# TPS63031_breakout.net
KiCad netlist of a schematic drawn in EAGLE
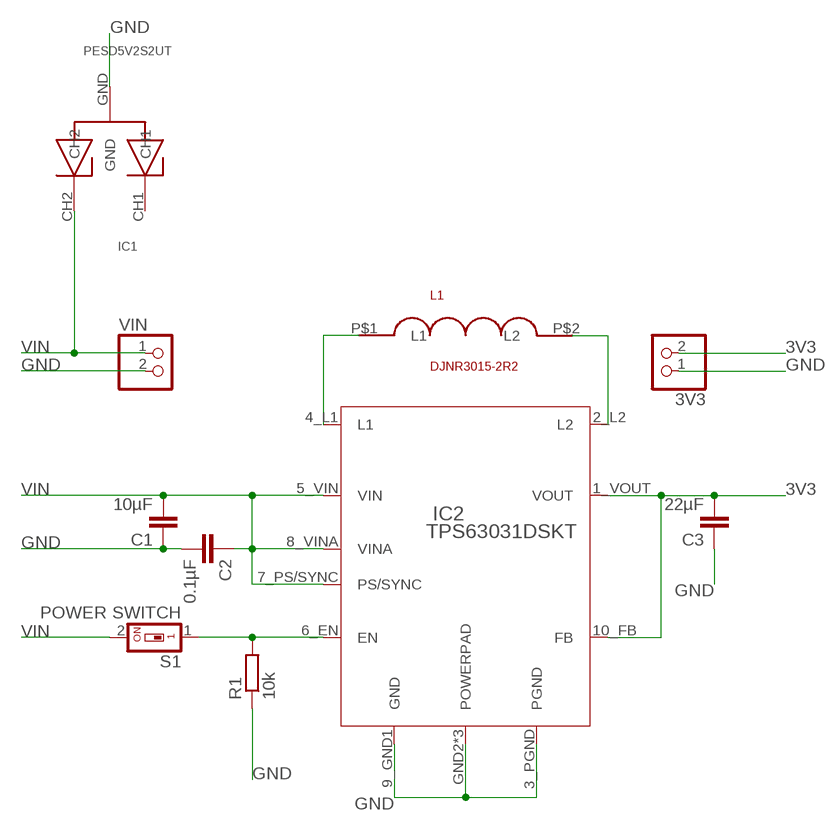
[diagram p0: schematic, sheet 1]

(export (version "E")
  (design (tool "Eeschema 10.0.6"))
  (components
    (comp (ref "3V3")
      (value "PINHD-1X2")
      (footprint "eagle-import:1X02")
      (libsource (lib "eagle-import") (part "PINHD-1X2"))
    )
    (comp (ref "C1")
      (value "10µF")
      (footprint "eagle-import:C0805")
      (libsource (lib "eagle-import") (part "C-EUC0805"))
    )
    (comp (ref "C2")
      (value "0.1µF")
      (footprint "eagle-import:C0805")
      (libsource (lib "eagle-import") (part "C-EUC0805"))
    )
    (comp (ref "C3")
      (value "22µF")
      (footprint "eagle-import:C0805")
      (libsource (lib "eagle-import") (part "C-EUC0805"))
    )
    (comp (ref "IC1")
      (value "PESD5V2S2UT")
      (footprint "eagle-import:SOT-23")
      (libsource (lib "eagle-import") (part "PESDXS2UT"))
    )
    (comp (ref "IC2")
      (value "TPS63031DSKT")
      (footprint "eagle-import:SMT")
      (libsource (lib "eagle-import") (part "TPS63031DSKT"))
    )
    (comp (ref "L1")
      (value "DJNR3015-2R2")
      (footprint "eagle-import:FFF")
      (libsource (lib "eagle-import") (part "DJNR3015-1R5"))
    )
    (comp (ref "R1")
      (value "10k")
      (footprint "eagle-import:R0805")
      (libsource (lib "eagle-import") (part "R-EU_R0805"))
    )
    (comp (ref "S1")
      (value "POWER SWITCH")
      (footprint "eagle-import:SMS-001")
      (libsource (lib "eagle-import") (part "SWS001"))
    )
    (comp (ref "VIN")
      (value "PINHD-1X2")
      (footprint "eagle-import:1X02")
      (libsource (lib "eagle-import") (part "PINHD-1X2"))
    )
  )
  (nets
    (net (code "1") (name "/3V3") (class "Default")
      (node (ref "3V3") (pin "2") (pinfunction "2_2") (pintype "passive"))
      (node (ref "C3") (pin "2") (pinfunction "2_2") (pintype "passive"))
      (node (ref "IC2") (pin "10_FB") (pinfunction "FB_10_FB") (pintype "passive"))
      (node (ref "IC2") (pin "1_VOUT") (pinfunction "VOUT_1_VOUT") (pintype "passive"))
    )
    (net (code "2") (name "/GND") (class "Default")
      (node (ref "3V3") (pin "1") (pinfunction "1_1") (pintype "passive"))
      (node (ref "C1") (pin "1") (pinfunction "1_1") (pintype "passive"))
      (node (ref "C2") (pin "2") (pinfunction "2_2") (pintype "passive"))
      (node (ref "C3") (pin "1") (pinfunction "1_1") (pintype "passive"))
      (node (ref "IC1") (pin "GND") (pinfunction "GND_GND") (pintype "bidirectional"))
      (node (ref "IC2") (pin "3_PGND") (pinfunction "PGND_3_PGND") (pintype "passive"))
      (node (ref "IC2") (pin "9_GND1") (pinfunction "GND_9_GND1") (pintype "passive"))
      (node (ref "IC2") (pin "GND2") (pinfunction "POWERPAD_GND2") (pintype "passive"))
      (node (ref "IC2") (pin "GND3") (pinfunction "POWERPAD_GND3") (pintype "passive"))
      (node (ref "IC2") (pin "GND4") (pinfunction "POWERPAD_GND4") (pintype "passive"))
      (node (ref "R1") (pin "1") (pinfunction "1_1") (pintype "passive"))
      (node (ref "VIN") (pin "2") (pinfunction "2_2") (pintype "passive"))
    )
    (net (code "3") (name "/VIN") (class "Default")
      (node (ref "C1") (pin "2") (pinfunction "2_2") (pintype "passive"))
      (node (ref "C2") (pin "1") (pinfunction "1_1") (pintype "passive"))
      (node (ref "IC1") (pin "CH2") (pinfunction "CH2_CH2") (pintype "bidirectional"))
      (node (ref "IC2") (pin "5_VIN") (pinfunction "VIN_5_VIN") (pintype "passive"))
      (node (ref "IC2") (pin "7_PS/SYNC") (pinfunction "PS/SYNC_7_PS/SYNC") (pintype "passive"))
      (node (ref "IC2") (pin "8_VINA") (pinfunction "VINA_8_VINA") (pintype "passive"))
      (node (ref "S1") (pin "2") (pinfunction "2_2") (pintype "passive"))
      (node (ref "VIN") (pin "1") (pinfunction "1_1") (pintype "passive"))
    )
    (net (code "4") (name "Net-(IC2-EN)") (class "Default")
      (node (ref "IC2") (pin "6_EN") (pinfunction "EN_6_EN") (pintype "passive"))
      (node (ref "R1") (pin "2") (pinfunction "2_2") (pintype "passive"))
      (node (ref "S1") (pin "1") (pinfunction "1_1") (pintype "passive"))
    )
    (net (code "5") (name "Net-(IC2-L1)") (class "Default")
      (node (ref "IC2") (pin "4_L1") (pinfunction "L1_4_L1") (pintype "passive"))
      (node (ref "L1") (pin "P$1") (pinfunction "L1_P$1") (pintype "bidirectional"))
    )
    (net (code "6") (name "Net-(IC2-L2)") (class "Default")
      (node (ref "IC2") (pin "2_L2") (pinfunction "L2_2_L2") (pintype "passive"))
      (node (ref "L1") (pin "P$2") (pinfunction "L2_P$2") (pintype "bidirectional"))
    )
    (net (code "7") (name "unconnected-(IC1-PadCH1)") (class "Default")
      (node (ref "IC1") (pin "CH1") (pinfunction "CH1_CH1") (pintype "bidirectional"))
    )
  )
)
